# rapidshark-lipo-sensor-mk-2_0.net
KiCad netlist of a schematic drawn in EAGLE
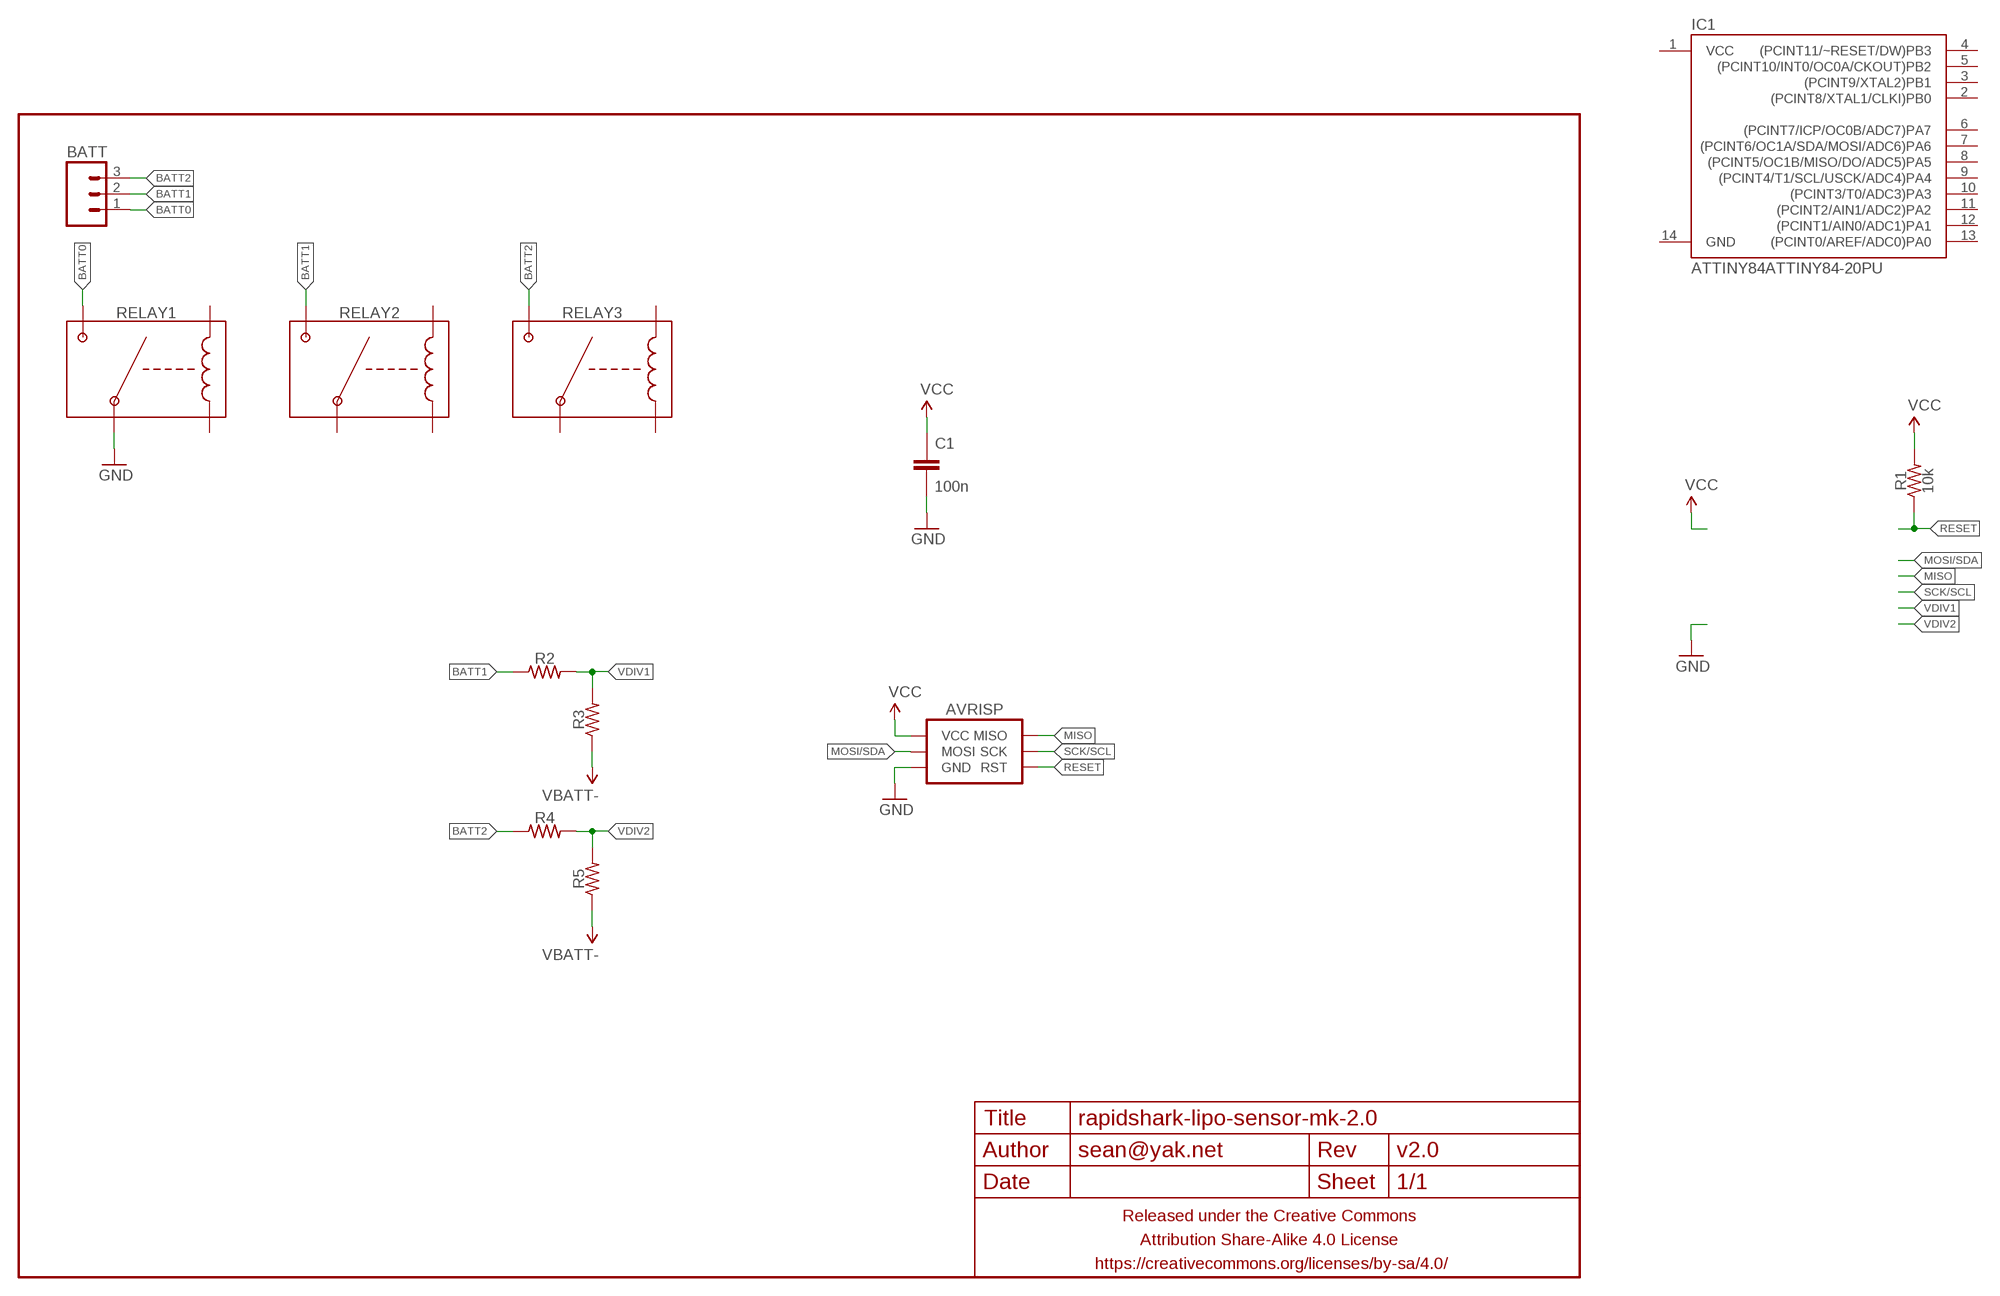
[diagram p0: schematic, sheet 1]

(export (version "E")
  (design (tool "Eeschema 10.0.6"))
  (components
    (comp (ref "AVRISP")
      (value "AVR_SPI_PRG_6PTH_INLINE_I2C")
      (footprint "eagle-import:AVR_ISP_INLINE_PTH_I2C")
      (libsource (lib "eagle-import") (part "AVR_SPI_PRG_6PTH_INLINE_I2C"))
    )
    (comp (ref "BATT")
      (value "M03PTH-CENTERED")
      (footprint "eagle-import:1X03-CENTERED")
      (libsource (lib "eagle-import") (part "M03PTH-CENTERED"))
    )
    (comp (ref "C1")
      (value "100n")
      (footprint "eagle-import:C025-024X044")
      (libsource (lib "eagle-import") (part "CAPACITOR-CERAMIC025-024X044"))
    )
    (comp (ref "FRAME1")
      (value "FRAME-LETTERNO_PACKAGE")
      (footprint "eagle-import:DUMMY")
      (fields (field (name "DESIGNER") "sean@yak.net") (field (name "VERSION") "v2.0"))
      (libsource (lib "eagle-import") (part "FRAME-LETTERNO_PACKAGE"))
    )
    (comp (ref "IC1")
      (value "ATTINY84ATTINY84-20PU")
      (footprint "eagle-import:DIL14")
      (libsource (lib "eagle-import") (part "ATTINY84ATTINY84-20PU"))
    )
    (comp (ref "R1")
      (value "10k")
      (footprint "eagle-import:RESISTOR-AXIAL-PTH-7.62MM")
      (libsource (lib "eagle-import") (part "RESISTORPTH-AXIAL-7.62MM"))
    )
    (comp (ref "R2")
      (value "RESISTORPTH-AXIAL-7.62MM")
      (footprint "eagle-import:RESISTOR-AXIAL-PTH-7.62MM")
      (libsource (lib "eagle-import") (part "RESISTORPTH-AXIAL-7.62MM"))
    )
    (comp (ref "R3")
      (value "RESISTORPTH-AXIAL-7.62MM")
      (footprint "eagle-import:RESISTOR-AXIAL-PTH-7.62MM")
      (libsource (lib "eagle-import") (part "RESISTORPTH-AXIAL-7.62MM"))
    )
    (comp (ref "R4")
      (value "RESISTORPTH-AXIAL-7.62MM")
      (footprint "eagle-import:RESISTOR-AXIAL-PTH-7.62MM")
      (libsource (lib "eagle-import") (part "RESISTORPTH-AXIAL-7.62MM"))
    )
    (comp (ref "R5")
      (value "RESISTORPTH-AXIAL-7.62MM")
      (footprint "eagle-import:RESISTOR-AXIAL-PTH-7.62MM")
      (libsource (lib "eagle-import") (part "RESISTORPTH-AXIAL-7.62MM"))
    )
    (comp (ref "RELAY1")
      (value "RELAY-SPST-NOCOTO-9007")
      (footprint "eagle-import:RELAY-SPST-NO-COTO-9007")
      (libsource (lib "eagle-import") (part "RELAY-SPST-NOCOTO-9007"))
    )
    (comp (ref "RELAY2")
      (value "RELAY-SPST-NOCOTO-9007")
      (footprint "eagle-import:RELAY-SPST-NO-COTO-9007")
      (libsource (lib "eagle-import") (part "RELAY-SPST-NOCOTO-9007"))
    )
    (comp (ref "RELAY3")
      (value "RELAY-SPST-NOCOTO-9007")
      (footprint "eagle-import:RELAY-SPST-NO-COTO-9007")
      (libsource (lib "eagle-import") (part "RELAY-SPST-NOCOTO-9007"))
    )
  )
  (nets
    (net (code "1") (name "BATT0") (class "Default")
      (node (ref "BATT") (pin "1") (pinfunction "1_1") (pintype "passive"))
      (node (ref "RELAY1") (pin "4") (pinfunction "NO_4") (pintype "bidirectional"))
    )
    (net (code "2") (name "BATT1") (class "Default")
      (node (ref "BATT") (pin "2") (pinfunction "2_2") (pintype "passive"))
      (node (ref "R2") (pin "P$1") (pinfunction "1_P$1") (pintype "passive"))
      (node (ref "RELAY2") (pin "4") (pinfunction "NO_4") (pintype "bidirectional"))
    )
    (net (code "3") (name "BATT2") (class "Default")
      (node (ref "BATT") (pin "3") (pinfunction "3_3") (pintype "passive"))
      (node (ref "R4") (pin "P$1") (pinfunction "1_P$1") (pintype "passive"))
      (node (ref "RELAY3") (pin "4") (pinfunction "NO_4") (pintype "bidirectional"))
    )
    (net (code "4") (name "GND") (class "Default")
      (node (ref "AVRISP") (pin "GND") (pinfunction "GND_GND") (pintype "passive"))
      (node (ref "C1") (pin "2") (pinfunction "2_2") (pintype "passive"))
      (node (ref "RELAY1") (pin "1") (pinfunction "COM_1") (pintype "bidirectional"))
    )
    (net (code "5") (name "MISO") (class "Default")
      (node (ref "AVRISP") (pin "MISO") (pinfunction "MISO_MISO") (pintype "passive"))
    )
    (net (code "6") (name "MOSI{slash}SDA") (class "Default")
      (node (ref "AVRISP") (pin "MOSI") (pinfunction "MOSI_MOSI") (pintype "passive"))
    )
    (net (code "7") (name "RESET") (class "Default")
      (node (ref "AVRISP") (pin "RESET") (pinfunction "RST_RESET") (pintype "passive"))
      (node (ref "R1") (pin "P$1") (pinfunction "1_P$1") (pintype "passive"))
    )
    (net (code "8") (name "SCK{slash}SCL") (class "Default")
      (node (ref "AVRISP") (pin "SCK") (pinfunction "SCK_SCK") (pintype "passive"))
    )
    (net (code "9") (name "VBATT-") (class "Default")
      (node (ref "R3") (pin "P$1") (pinfunction "1_P$1") (pintype "passive"))
      (node (ref "R5") (pin "P$1") (pinfunction "1_P$1") (pintype "passive"))
    )
    (net (code "10") (name "VCC") (class "Default")
      (node (ref "AVRISP") (pin "VCC") (pinfunction "VCC_VCC") (pintype "passive"))
      (node (ref "C1") (pin "1") (pinfunction "1_1") (pintype "passive"))
      (node (ref "R1") (pin "P$2") (pinfunction "2_P$2") (pintype "passive"))
    )
    (net (code "11") (name "VDIV1") (class "Default")
      (node (ref "R2") (pin "P$2") (pinfunction "2_P$2") (pintype "passive"))
      (node (ref "R3") (pin "P$2") (pinfunction "2_P$2") (pintype "passive"))
    )
    (net (code "12") (name "VDIV2") (class "Default")
      (node (ref "R4") (pin "P$2") (pinfunction "2_P$2") (pintype "passive"))
      (node (ref "R5") (pin "P$2") (pinfunction "2_P$2") (pintype "passive"))
    )
    (net (code "13") (name "unconnected-(IC1-(PCINT0{slash}AREF{slash}ADC0)PA0-Pad13)") (class "Default")
      (node (ref "IC1") (pin "13") (pinfunction "(PCINT0/AREF/ADC0)PA0_13") (pintype "bidirectional"))
    )
    (net (code "14") (name "unconnected-(IC1-(PCINT1{slash}AIN0{slash}ADC1)PA1-Pad12)") (class "Default")
      (node (ref "IC1") (pin "12") (pinfunction "(PCINT1/AIN0/ADC1)PA1_12") (pintype "bidirectional"))
    )
    (net (code "15") (name "unconnected-(IC1-(PCINT2{slash}AIN1{slash}ADC2)PA2-Pad11)") (class "Default")
      (node (ref "IC1") (pin "11") (pinfunction "(PCINT2/AIN1/ADC2)PA2_11") (pintype "bidirectional"))
    )
    (net (code "16") (name "unconnected-(IC1-(PCINT3{slash}T0{slash}ADC3)PA3-Pad10)") (class "Default")
      (node (ref "IC1") (pin "10") (pinfunction "(PCINT3/T0/ADC3)PA3_10") (pintype "bidirectional"))
    )
    (net (code "17") (name "unconnected-(IC1-(PCINT4{slash}T1{slash}SCL{slash}USCK{slash}ADC4)PA4-Pad9)") (class "Default")
      (node (ref "IC1") (pin "9") (pinfunction "(PCINT4/T1/SCL/USCK/ADC4)PA4_9") (pintype "bidirectional"))
    )
    (net (code "18") (name "unconnected-(IC1-(PCINT5{slash}OC1B{slash}MISO{slash}DO{slash}ADC5)PA5-Pad8)") (class "Default")
      (node (ref "IC1") (pin "8") (pinfunction "(PCINT5/OC1B/MISO/DO/ADC5)PA5_8") (pintype "bidirectional"))
    )
    (net (code "19") (name "unconnected-(IC1-(PCINT6{slash}OC1A{slash}SDA{slash}MOSI{slash}ADC6)PA6-Pad7)") (class "Default")
      (node (ref "IC1") (pin "7") (pinfunction "(PCINT6/OC1A/SDA/MOSI/ADC6)PA6_7") (pintype "bidirectional"))
    )
    (net (code "20") (name "unconnected-(IC1-(PCINT7{slash}ICP{slash}OC0B{slash}ADC7)PA7-Pad6)") (class "Default")
      (node (ref "IC1") (pin "6") (pinfunction "(PCINT7/ICP/OC0B/ADC7)PA7_6") (pintype "bidirectional"))
    )
    (net (code "21") (name "unconnected-(IC1-(PCINT8{slash}XTAL1{slash}CLKI)PB0-Pad2)") (class "Default")
      (node (ref "IC1") (pin "2") (pinfunction "(PCINT8/XTAL1/CLKI)PB0_2") (pintype "bidirectional"))
    )
    (net (code "22") (name "unconnected-(IC1-(PCINT9{slash}XTAL2)PB1-Pad3)") (class "Default")
      (node (ref "IC1") (pin "3") (pinfunction "(PCINT9/XTAL2)PB1_3") (pintype "bidirectional"))
    )
    (net (code "23") (name "unconnected-(IC1-(PCINT10{slash}INT0{slash}OC0A{slash}CKOUT)PB2-Pad5)") (class "Default")
      (node (ref "IC1") (pin "5") (pinfunction "(PCINT10/INT0/OC0A/CKOUT)PB2_5") (pintype "bidirectional"))
    )
    (net (code "24") (name "unconnected-(IC1-(PCINT11{slash}~{RESET{slash}DW})PB3-Pad4)") (class "Default")
      (node (ref "IC1") (pin "4") (pinfunction "(PCINT11/~{RESET/DW})PB3_4") (pintype "bidirectional"))
    )
    (net (code "25") (name "unconnected-(IC1-GND-Pad14)") (class "Default")
      (node (ref "IC1") (pin "14") (pinfunction "GND_14") (pintype "bidirectional"))
    )
    (net (code "26") (name "unconnected-(IC1-VCC-Pad1)") (class "Default")
      (node (ref "IC1") (pin "1") (pinfunction "VCC_1") (pintype "bidirectional"))
    )
    (net (code "27") (name "unconnected-(RELAY1-C$1-Pad2)") (class "Default")
      (node (ref "RELAY1") (pin "2") (pinfunction "C$1_2") (pintype "bidirectional"))
    )
    (net (code "28") (name "unconnected-(RELAY1-C$2-Pad3)") (class "Default")
      (node (ref "RELAY1") (pin "3") (pinfunction "C$2_3") (pintype "bidirectional"))
    )
    (net (code "29") (name "unconnected-(RELAY2-C$1-Pad2)") (class "Default")
      (node (ref "RELAY2") (pin "2") (pinfunction "C$1_2") (pintype "bidirectional"))
    )
    (net (code "30") (name "unconnected-(RELAY2-C$2-Pad3)") (class "Default")
      (node (ref "RELAY2") (pin "3") (pinfunction "C$2_3") (pintype "bidirectional"))
    )
    (net (code "31") (name "unconnected-(RELAY2-COM-Pad1)") (class "Default")
      (node (ref "RELAY2") (pin "1") (pinfunction "COM_1") (pintype "bidirectional"))
    )
    (net (code "32") (name "unconnected-(RELAY3-C$1-Pad2)") (class "Default")
      (node (ref "RELAY3") (pin "2") (pinfunction "C$1_2") (pintype "bidirectional"))
    )
    (net (code "33") (name "unconnected-(RELAY3-C$2-Pad3)") (class "Default")
      (node (ref "RELAY3") (pin "3") (pinfunction "C$2_3") (pintype "bidirectional"))
    )
    (net (code "34") (name "unconnected-(RELAY3-COM-Pad1)") (class "Default")
      (node (ref "RELAY3") (pin "1") (pinfunction "COM_1") (pintype "bidirectional"))
    )
  )
)
